# B4_FM__X_SOLAR_PANEL_v2.net
KiCad netlist of a schematic drawn in EAGLE
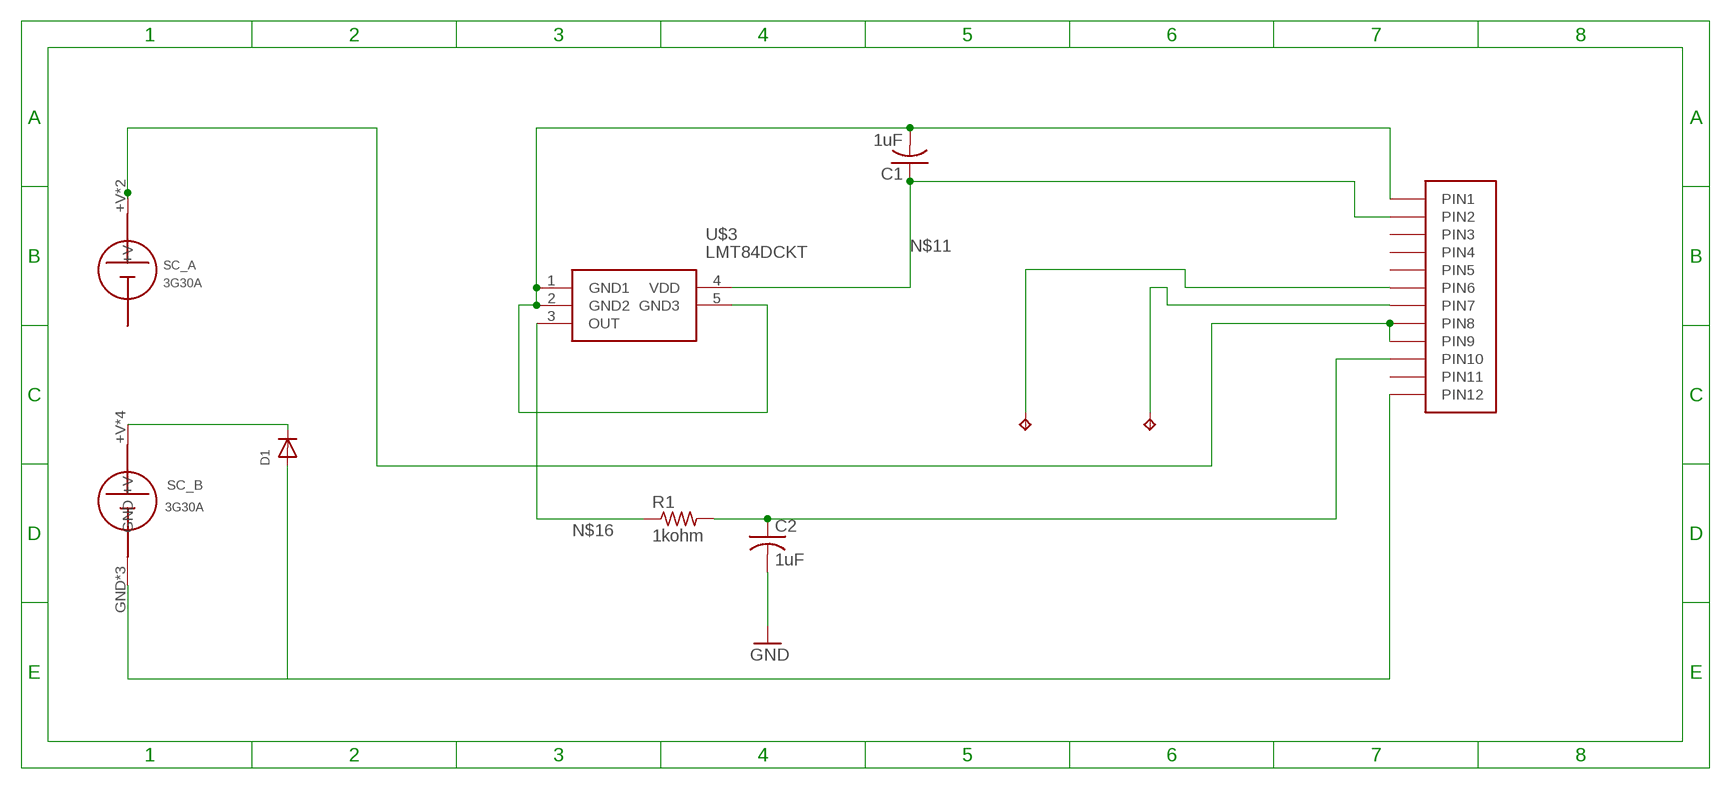
[diagram p0: schematic, sheet 1]

(export (version "E")
  (design (tool "Eeschema 10.0.6"))
  (components
    (comp (ref "C1")
      (value "1uF")
      (footprint "eagle-import:C0805")
      (libsource (lib "eagle-import") (part "C-USC0805"))
    )
    (comp (ref "C2")
      (value "1uF")
      (footprint "eagle-import:C0805")
      (libsource (lib "eagle-import") (part "C-USC0805"))
    )
    (comp (ref "D1")
      (value "DIODE_SOD-123FL")
      (footprint "eagle-import:SOD-123FL")
      (libsource (lib "eagle-import") (part "DIODE_SOD-123FL"))
    )
    (comp (ref "R1")
      (value "1kohm")
      (footprint "eagle-import:R0402")
      (libsource (lib "eagle-import") (part "R-US_R0402"))
    )
    (comp (ref "SDA1")
      (value "S1751-46R")
      (footprint "eagle-import:S1751-46R")
      (libsource (lib "eagle-import") (part "S1751-46R"))
    )
    (comp (ref "SDA3")
      (value "S1751-46R")
      (footprint "eagle-import:S1751-46R")
      (libsource (lib "eagle-import") (part "S1751-46R"))
    )
    (comp (ref "SOLARCELL_A")
      (value "SC_A")
      (footprint "eagle-import:SC_A")
      (libsource (lib "eagle-import") (part "SC_A"))
    )
    (comp (ref "SOLARCELL_B")
      (value "SC_B")
      (footprint "eagle-import:SC_B")
      (libsource (lib "eagle-import") (part "SC_B"))
    )
    (comp (ref "U$1")
      (value "HEADER12PIN")
      (footprint "eagle-import:HEADER12PIN")
      (libsource (lib "eagle-import") (part "HEADER12PIN"))
    )
    (comp (ref "U$3")
      (value "LMT84DCKT")
      (footprint "eagle-import:SOT65P210X110-5N")
      (fields (field (name "RS_PART_NUMBER") "8115860"))
      (libsource (lib "eagle-import") (part "LMT84DCKT"))
    )
  )
  (nets
    (net (code "1") (name "/N$11") (class "Default")
      (node (ref "C1") (pin "1") (pinfunction "1_1") (pintype "passive"))
      (node (ref "U$1") (pin "P2") (pinfunction "PIN2_P2") (pintype "bidirectional"))
      (node (ref "U$3") (pin "4") (pinfunction "VDD_4") (pintype "power_in"))
    )
    (net (code "2") (name "/N$16") (class "Default")
      (node (ref "R1") (pin "1") (pinfunction "1_1") (pintype "passive"))
      (node (ref "U$3") (pin "3") (pinfunction "OUT_3") (pintype "output"))
    )
    (net (code "3") (name "GND") (class "Default")
      (node (ref "C1") (pin "2") (pinfunction "2_2") (pintype "passive"))
      (node (ref "C2") (pin "2") (pinfunction "2_2") (pintype "passive"))
      (node (ref "D1") (pin "A") (pinfunction "A_A") (pintype "passive"))
      (node (ref "SOLARCELL_B") (pin "GND") (pinfunction "GND_GND") (pintype "bidirectional"))
      (node (ref "SOLARCELL_B") (pin "GND1") (pinfunction "GND_GND1") (pintype "bidirectional"))
      (node (ref "SOLARCELL_B") (pin "GND2") (pinfunction "GND_GND2") (pintype "bidirectional"))
      (node (ref "U$1") (pin "P1") (pinfunction "PIN1_P1") (pintype "bidirectional"))
      (node (ref "U$1") (pin "P12") (pinfunction "PIN12_P12") (pintype "bidirectional"))
      (node (ref "U$3") (pin "1") (pinfunction "GND1_1") (pintype "power_in"))
      (node (ref "U$3") (pin "2") (pinfunction "GND2_2") (pintype "power_in"))
      (node (ref "U$3") (pin "5") (pinfunction "GND3_5") (pintype "power_in"))
    )
    (net (code "4") (name "Net-(D1-PadC)") (class "Default")
      (node (ref "D1") (pin "C") (pinfunction "C_C") (pintype "passive"))
      (node (ref "SOLARCELL_B") (pin "+V") (pinfunction "+V_+V") (pintype "bidirectional"))
      (node (ref "SOLARCELL_B") (pin "+V2") (pinfunction "+V_+V2") (pintype "bidirectional"))
      (node (ref "SOLARCELL_B") (pin "+V3") (pinfunction "+V_+V3") (pintype "bidirectional"))
      (node (ref "SOLARCELL_B") (pin "+V4") (pinfunction "+V_+V4") (pintype "bidirectional"))
    )
    (net (code "5") (name "Net-(SDA1-TP)") (class "Default")
      (node (ref "SDA1") (pin "P$1") (pinfunction "TP_P$1") (pintype "input"))
      (node (ref "U$1") (pin "P6") (pinfunction "PIN6_P6") (pintype "bidirectional"))
    )
    (net (code "6") (name "Net-(SDA3-TP)") (class "Default")
      (node (ref "SDA3") (pin "P$1") (pinfunction "TP_P$1") (pintype "input"))
      (node (ref "U$1") (pin "P7") (pinfunction "PIN7_P7") (pintype "bidirectional"))
    )
    (net (code "7") (name "Net-(U$1-PIN8)") (class "Default")
      (node (ref "SOLARCELL_A") (pin "+V") (pinfunction "+V_+V") (pintype "bidirectional"))
      (node (ref "SOLARCELL_A") (pin "+V1") (pinfunction "+V_+V1") (pintype "bidirectional"))
      (node (ref "U$1") (pin "P8") (pinfunction "PIN8_P8") (pintype "bidirectional"))
      (node (ref "U$1") (pin "P9") (pinfunction "PIN9_P9") (pintype "bidirectional"))
    )
    (net (code "8") (name "Net-(U$1-PIN10)") (class "Default")
      (node (ref "C2") (pin "1") (pinfunction "1_1") (pintype "passive"))
      (node (ref "R1") (pin "2") (pinfunction "2_2") (pintype "passive"))
      (node (ref "U$1") (pin "P10") (pinfunction "PIN10_P10") (pintype "bidirectional"))
    )
    (net (code "9") (name "unconnected-(U$1-PIN3-PadP3)") (class "Default")
      (node (ref "U$1") (pin "P3") (pinfunction "PIN3_P3") (pintype "bidirectional"))
    )
    (net (code "10") (name "unconnected-(U$1-PIN4-PadP4)") (class "Default")
      (node (ref "U$1") (pin "P4") (pinfunction "PIN4_P4") (pintype "bidirectional"))
    )
    (net (code "11") (name "unconnected-(U$1-PIN5-PadP5)") (class "Default")
      (node (ref "U$1") (pin "P5") (pinfunction "PIN5_P5") (pintype "bidirectional"))
    )
    (net (code "12") (name "unconnected-(U$1-PIN11-PadP11)") (class "Default")
      (node (ref "U$1") (pin "P11") (pinfunction "PIN11_P11") (pintype "bidirectional"))
    )
  )
)
